# DirtyPWMSim.net
KiCad netlist of a schematic drawn in Altium Designer
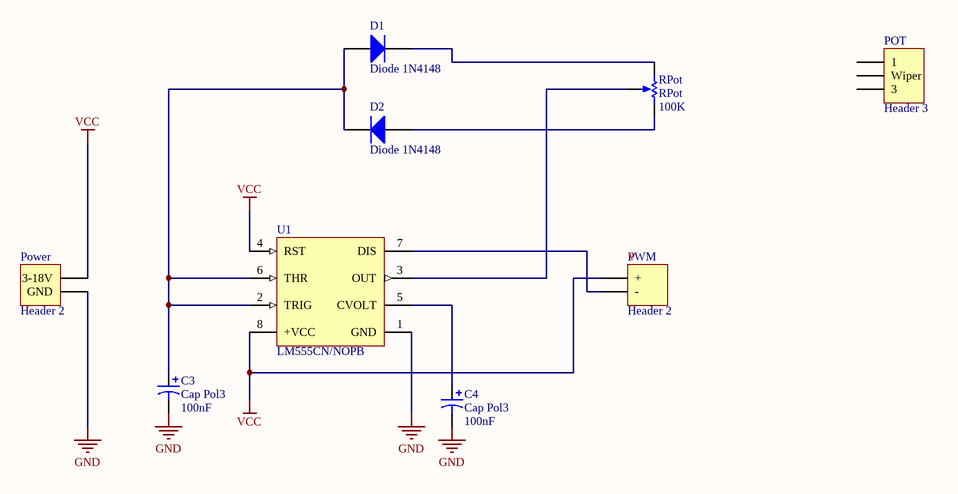
[diagram p0: DirtyPWMSim.SchDoc]

(export (version "E")
  (design (tool "Eeschema 10.0.6"))
  (components
    (comp (ref "C3")
      (value "Cap Pol3")
      (footprint "C0805")
      (description "Polarized Capacitor (Surface Mount)")
      (fields (field (name "ALTIUM_VALUE") "100nF") (field (name "PUBLISHER") "Altium Limited"))
      (libsource (lib "Miscellaneous Devices") (part "Cap Pol3"))
    )
    (comp (ref "C4")
      (value "Cap Pol3")
      (footprint "C0805")
      (description "Polarized Capacitor (Surface Mount)")
      (fields (field (name "ALTIUM_VALUE") "100nF") (field (name "PUBLISHER") "Altium Limited"))
      (libsource (lib "Miscellaneous Devices") (part "Cap Pol3"))
    )
    (comp (ref "D1")
      (value "Diode 1N4148")
      (footprint "DO-35")
      (description "High Conductance Fast Diode")
      (fields (field (name "PUBLISHER") "Altium Limited"))
      (libsource (lib "Miscellaneous Devices") (part "Diode 1N4148"))
    )
    (comp (ref "D2")
      (value "Diode 1N4148")
      (footprint "DO-35")
      (description "High Conductance Fast Diode")
      (fields (field (name "PUBLISHER") "Altium Limited"))
      (libsource (lib "Miscellaneous Devices") (part "Diode 1N4148"))
    )
    (comp (ref "POT")
      (value "Header 3")
      (footprint "HDR1X3")
      (description "Header, 3-Pin")
      (fields (field (name "PUBLISHER") "Altium Limited"))
      (libsource (lib "Miscellaneous Connectors") (part "Header 3"))
    )
    (comp (ref "Power")
      (value "Header 2")
      (footprint "HDR1X2")
      (description "Header, 2-Pin")
      (fields (field (name "PUBLISHER") "Altium Limited"))
      (libsource (lib "Miscellaneous Connectors") (part "Header 2"))
    )
    (comp (ref "PWM")
      (value "Header 2")
      (footprint "HDR1X2")
      (description "Header, 2-Pin")
      (fields (field (name "PUBLISHER") "Altium Limited"))
      (libsource (lib "") (part "Header 2_1"))
    )
    (comp (ref "RPot")
      (value "RPot")
      (footprint "VR5")
      (description "Potentiometer")
      (fields (field (name "ALTIUM_VALUE") "100K") (field (name "PUBLISHER") "Altium Limited"))
      (libsource (lib "Miscellaneous Devices") (part "RPot"))
    )
    (comp (ref "U1")
      (value "LM555CN/NOPB")
      (footprint "N08E")
      (description "Timer, 8-pin MDIP, Pb-Free")
      (fields (field (name "MANUFACTURER") "National Semiconductor"))
      (libsource (lib "Altium Content Vault") (part "AN-TIMER-LM555-8"))
    )
  )
  (nets
    (net (code "1") (name "GND") (class "Default")
      (node (ref "C3") (pin "2") (pinfunction "2_2") (pintype "passive"))
      (node (ref "C4") (pin "2") (pinfunction "2_2") (pintype "passive"))
      (node (ref "Power") (pin "2") (pinfunction "GND_2") (pintype "passive"))
      (node (ref "U1") (pin "1") (pinfunction "GND_1") (pintype "power_in"))
    )
    (net (code "2") (name "Net-(D1-A)") (class "Default")
      (node (ref "C3") (pin "1") (pinfunction "1_1") (pintype "passive"))
      (node (ref "D1") (pin "1") (pinfunction "A_1") (pintype "passive"))
      (node (ref "D2") (pin "2") (pinfunction "K_2") (pintype "passive"))
      (node (ref "U1") (pin "2") (pinfunction "TRIG_2") (pintype "input"))
      (node (ref "U1") (pin "6") (pinfunction "THR_6") (pintype "input"))
    )
    (net (code "3") (name "Net-(D1-K)") (class "Default")
      (node (ref "D1") (pin "2") (pinfunction "K_2") (pintype "passive"))
      (node (ref "RPot") (pin "1") (pinfunction "TOP_1") (pintype "passive"))
    )
    (net (code "4") (name "Net-(D2-A)") (class "Default")
      (node (ref "D2") (pin "1") (pinfunction "A_1") (pintype "passive"))
      (node (ref "RPot") (pin "2") (pinfunction "BOT_2") (pintype "passive"))
    )
    (net (code "5") (name "Net-(PWM--)") (class "Default")
      (node (ref "PWM") (pin "2") (pinfunction "-_2") (pintype "passive"))
      (node (ref "U1") (pin "7") (pinfunction "DIS_7") (pintype "open_collector"))
    )
    (net (code "6") (name "Net-(RPot-TAP)") (class "Default")
      (node (ref "RPot") (pin "3") (pinfunction "TAP_3") (pintype "passive"))
      (node (ref "U1") (pin "3") (pinfunction "OUT_3") (pintype "output"))
    )
    (net (code "7") (name "Net-(U1-CVOLT)") (class "Default")
      (node (ref "C4") (pin "1") (pinfunction "1_1") (pintype "passive"))
      (node (ref "U1") (pin "5") (pinfunction "CVOLT_5") (pintype "passive"))
    )
    (net (code "8") (name "VCC") (class "Default")
      (node (ref "PWM") (pin "1") (pinfunction "+_1") (pintype "passive"))
      (node (ref "Power") (pin "1") (pinfunction "3-18V_1") (pintype "passive"))
      (node (ref "U1") (pin "4") (pinfunction "RST_4") (pintype "input"))
      (node (ref "U1") (pin "8") (pinfunction "+VCC_8") (pintype "power_in"))
    )
    (net (code "9") (name "unconnected-(POT-Pad1)") (class "Default")
      (node (ref "POT") (pin "1") (pinfunction "1_1") (pintype "passive"))
    )
    (net (code "10") (name "unconnected-(POT-Pad3)") (class "Default")
      (node (ref "POT") (pin "3") (pinfunction "3_3") (pintype "passive"))
    )
    (net (code "11") (name "unconnected-(POT-Wiper-Pad2)") (class "Default")
      (node (ref "POT") (pin "2") (pinfunction "Wiper_2") (pintype "passive"))
    )
  )
)
